# VLP_FPC.net
KiCad netlist of a schematic drawn in Altium Designer
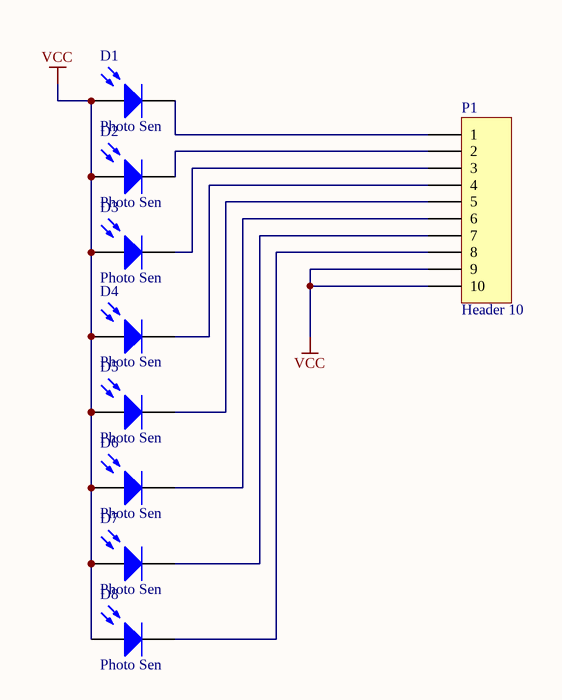
[diagram p0: VLP_FPC.SchDoc]

(export (version "E")
  (design (tool "Eeschema 10.0.6"))
  (components
    (comp (ref "D1")
      (value "Photo Sen")
      (footprint "1206C")
      (description "Photosensitive Diode")
      (fields (field (name "PUBLISHER") "Altium Limited"))
      (libsource (lib "Miscellaneous Devices") (part "Photo Sen"))
    )
    (comp (ref "D2")
      (value "Photo Sen")
      (footprint "1206C")
      (description "Photosensitive Diode")
      (fields (field (name "PUBLISHER") "Altium Limited"))
      (libsource (lib "Miscellaneous Devices") (part "Photo Sen"))
    )
    (comp (ref "D3")
      (value "Photo Sen")
      (footprint "1206C")
      (description "Photosensitive Diode")
      (fields (field (name "PUBLISHER") "Altium Limited"))
      (libsource (lib "Miscellaneous Devices") (part "Photo Sen"))
    )
    (comp (ref "D4")
      (value "Photo Sen")
      (footprint "1206C")
      (description "Photosensitive Diode")
      (fields (field (name "PUBLISHER") "Altium Limited"))
      (libsource (lib "Miscellaneous Devices") (part "Photo Sen"))
    )
    (comp (ref "D5")
      (value "Photo Sen")
      (footprint "1206C")
      (description "Photosensitive Diode")
      (fields (field (name "PUBLISHER") "Altium Limited"))
      (libsource (lib "Miscellaneous Devices") (part "Photo Sen"))
    )
    (comp (ref "D6")
      (value "Photo Sen")
      (footprint "1206C")
      (description "Photosensitive Diode")
      (fields (field (name "PUBLISHER") "Altium Limited"))
      (libsource (lib "Miscellaneous Devices") (part "Photo Sen"))
    )
    (comp (ref "D7")
      (value "Photo Sen")
      (footprint "1206C")
      (description "Photosensitive Diode")
      (fields (field (name "PUBLISHER") "Altium Limited"))
      (libsource (lib "Miscellaneous Devices") (part "Photo Sen"))
    )
    (comp (ref "D8")
      (value "Photo Sen")
      (footprint "1206C")
      (description "Photosensitive Diode")
      (fields (field (name "PUBLISHER") "Altium Limited"))
      (libsource (lib "Miscellaneous Devices") (part "Photo Sen"))
    )
    (comp (ref "P1")
      (value "Header 10")
      (footprint "FPC-10P")
      (description "Header, 10-Pin")
      (fields (field (name "PUBLISHER") "Altium Limited"))
      (libsource (lib "Miscellaneous Connectors") (part "Header 10"))
    )
  )
  (nets
    (net (code "1") (name "Net-(D1-K)") (class "Default")
      (node (ref "D1") (pin "2") (pinfunction "K_2") (pintype "passive"))
      (node (ref "P1") (pin "1") (pinfunction "1_1") (pintype "passive"))
    )
    (net (code "2") (name "Net-(D2-K)") (class "Default")
      (node (ref "D2") (pin "2") (pinfunction "K_2") (pintype "passive"))
      (node (ref "P1") (pin "2") (pinfunction "2_2") (pintype "passive"))
    )
    (net (code "3") (name "Net-(D3-K)") (class "Default")
      (node (ref "D3") (pin "2") (pinfunction "K_2") (pintype "passive"))
      (node (ref "P1") (pin "3") (pinfunction "3_3") (pintype "passive"))
    )
    (net (code "4") (name "Net-(D4-K)") (class "Default")
      (node (ref "D4") (pin "2") (pinfunction "K_2") (pintype "passive"))
      (node (ref "P1") (pin "4") (pinfunction "4_4") (pintype "passive"))
    )
    (net (code "5") (name "Net-(D5-K)") (class "Default")
      (node (ref "D5") (pin "2") (pinfunction "K_2") (pintype "passive"))
      (node (ref "P1") (pin "5") (pinfunction "5_5") (pintype "passive"))
    )
    (net (code "6") (name "Net-(D6-K)") (class "Default")
      (node (ref "D6") (pin "2") (pinfunction "K_2") (pintype "passive"))
      (node (ref "P1") (pin "6") (pinfunction "6_6") (pintype "passive"))
    )
    (net (code "7") (name "Net-(D7-K)") (class "Default")
      (node (ref "D7") (pin "2") (pinfunction "K_2") (pintype "passive"))
      (node (ref "P1") (pin "7") (pinfunction "7_7") (pintype "passive"))
    )
    (net (code "8") (name "Net-(D8-K)") (class "Default")
      (node (ref "D8") (pin "2") (pinfunction "K_2") (pintype "passive"))
      (node (ref "P1") (pin "8") (pinfunction "8_8") (pintype "passive"))
    )
    (net (code "9") (name "VCC") (class "Default")
      (node (ref "D1") (pin "1") (pinfunction "A_1") (pintype "passive"))
      (node (ref "D2") (pin "1") (pinfunction "A_1") (pintype "passive"))
      (node (ref "D3") (pin "1") (pinfunction "A_1") (pintype "passive"))
      (node (ref "D4") (pin "1") (pinfunction "A_1") (pintype "passive"))
      (node (ref "D5") (pin "1") (pinfunction "A_1") (pintype "passive"))
      (node (ref "D6") (pin "1") (pinfunction "A_1") (pintype "passive"))
      (node (ref "D7") (pin "1") (pinfunction "A_1") (pintype "passive"))
      (node (ref "D8") (pin "1") (pinfunction "A_1") (pintype "passive"))
      (node (ref "P1") (pin "10") (pinfunction "10_10") (pintype "passive"))
      (node (ref "P1") (pin "9") (pinfunction "9_9") (pintype "passive"))
    )
  )
)
